# VisualightMicroDIY_02.net
KiCad netlist of a schematic drawn in EAGLE
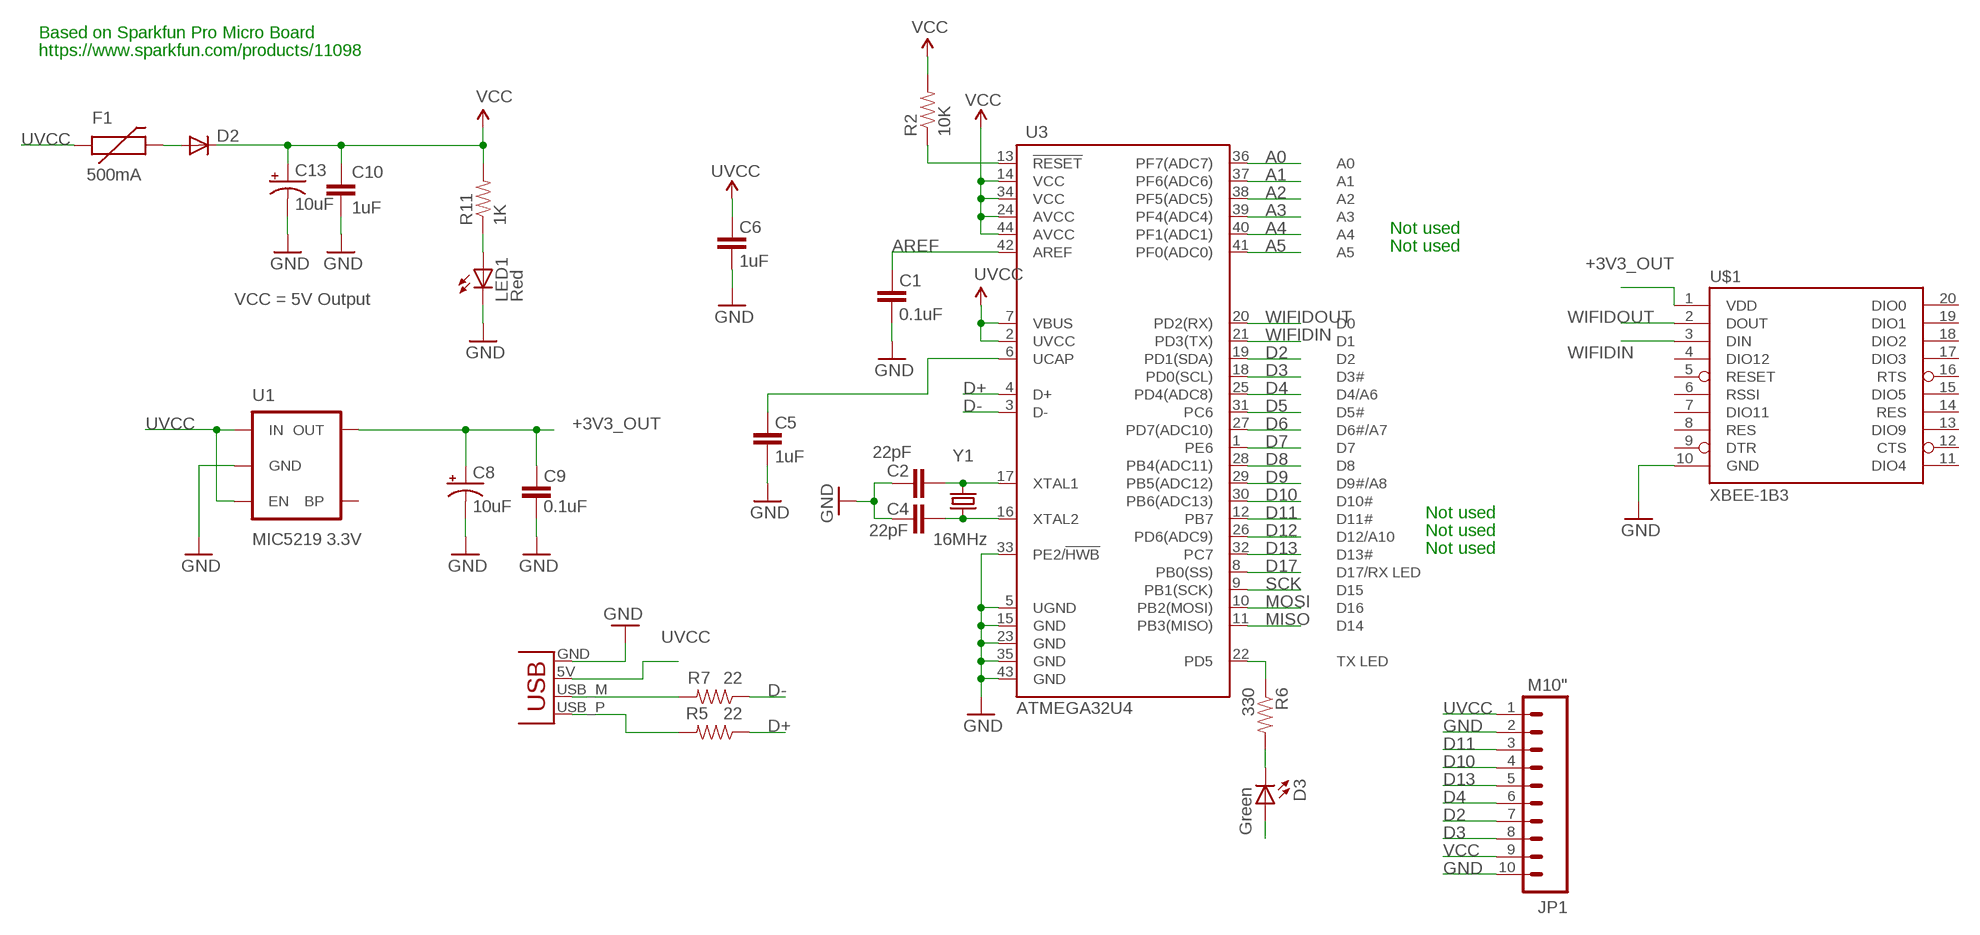
[diagram p0: schematic, sheet 1]

(export (version "E")
  (design (tool "Eeschema 10.0.6"))
  (components
    (comp (ref "C1")
      (value "0.1uF")
      (footprint "eagle-import:0402-CAP")
      (libsource (lib "eagle-import") (part "CAP0402-CAP"))
    )
    (comp (ref "C2")
      (value "22pF")
      (footprint "eagle-import:0402-CAP")
      (libsource (lib "eagle-import") (part "CAP0402-CAP"))
    )
    (comp (ref "C4")
      (value "22pF")
      (footprint "eagle-import:0402-CAP")
      (libsource (lib "eagle-import") (part "CAP0402-CAP"))
    )
    (comp (ref "C5")
      (value "1uF")
      (footprint "eagle-import:0402-CAP")
      (libsource (lib "eagle-import") (part "CAP0402-CAP"))
    )
    (comp (ref "C6")
      (value "1uF")
      (footprint "eagle-import:0402-CAP")
      (libsource (lib "eagle-import") (part "CAP0402-CAP"))
    )
    (comp (ref "C8")
      (value "10uF")
      (footprint "eagle-import:EIA3216")
      (libsource (lib "eagle-import") (part "CAP_POL1206"))
    )
    (comp (ref "C9")
      (value "0.1uF")
      (footprint "eagle-import:0402-CAP")
      (libsource (lib "eagle-import") (part "CAP0402-CAP"))
    )
    (comp (ref "C10")
      (value "1uF")
      (footprint "eagle-import:0402-CAP")
      (libsource (lib "eagle-import") (part "CAP0402-CAP"))
    )
    (comp (ref "C13")
      (value "10uF")
      (footprint "eagle-import:EIA3216")
      (libsource (lib "eagle-import") (part "CAP_POL1206"))
    )
    (comp (ref "D2")
      (value "DIODESOD")
      (footprint "eagle-import:SOD-323")
      (libsource (lib "eagle-import") (part "DIODESOD"))
    )
    (comp (ref "D3")
      (value "Green")
      (footprint "eagle-import:LED-0603")
      (libsource (lib "eagle-import") (part "LED0603"))
    )
    (comp (ref "F1")
      (value "500mA")
      (footprint "eagle-import:PTC-1206")
      (libsource (lib "eagle-import") (part "PTCSMD"))
    )
    (comp (ref "JP1")
      (value "M10\"")
      (footprint "eagle-import:1X10")
      (libsource (lib "eagle-import") (part "M10{dblquote}"))
    )
    (comp (ref "LED1")
      (value "Red")
      (footprint "eagle-import:LED-0603")
      (libsource (lib "eagle-import") (part "LED0603"))
    )
    (comp (ref "R2")
      (value "10K")
      (footprint "eagle-import:0402-RES")
      (libsource (lib "eagle-import") (part "RESISTOR0402-RES"))
    )
    (comp (ref "R5")
      (value "22")
      (footprint "eagle-import:0402-RES")
      (libsource (lib "eagle-import") (part "RESISTOR0402-RES"))
    )
    (comp (ref "R6")
      (value "330")
      (footprint "eagle-import:0402-RES")
      (libsource (lib "eagle-import") (part "RESISTOR0402-RES"))
    )
    (comp (ref "R7")
      (value "22")
      (footprint "eagle-import:0402-RES")
      (libsource (lib "eagle-import") (part "RESISTOR0402-RES"))
    )
    (comp (ref "R11")
      (value "1K")
      (footprint "eagle-import:0402-RES")
      (libsource (lib "eagle-import") (part "RESISTOR0402-RES"))
    )
    (comp (ref "U$1")
      (value "XBEE-1B3")
      (footprint "eagle-import:XBEE-SMD")
      (libsource (lib "eagle-import") (part "XBEE-1B3"))
    )
    (comp (ref "U1")
      (value "MIC5219 3.3V")
      (footprint "eagle-import:SOT23-5")
      (libsource (lib "eagle-import") (part "V_REG_MIC52193.3V"))
    )
    (comp (ref "U3")
      (value "ATMEGA32U4")
      (footprint "eagle-import:SPARKFUN-DIGITALIC_TQFP44")
      (libsource (lib "eagle-import") (part "ATMEGA32U4TQFP"))
    )
    (comp (ref "X2")
      (value "USBPCB")
      (footprint "eagle-import:USB-A-PCB")
      (libsource (lib "eagle-import") (part "USBPCB"))
    )
    (comp (ref "Y1")
      (value "16MHz")
      (footprint "eagle-import:CRYSTAL-SMD-5X3")
      (libsource (lib "eagle-import") (part "CRYSTAL5X3"))
    )
  )
  (nets
    (net (code "1") (name "/+3V3_OUT") (class "Default")
      (node (ref "C8") (pin "A") (pinfunction "+_A") (pintype "passive"))
      (node (ref "C9") (pin "2") (pinfunction "2_2") (pintype "passive"))
      (node (ref "U$1") (pin "1") (pinfunction "VDD_1") (pintype "power_in"))
      (node (ref "U1") (pin "5") (pinfunction "OUT_5") (pintype "passive"))
    )
    (net (code "2") (name "/A0") (class "Default")
      (node (ref "U3") (pin "36") (pinfunction "PF7(ADC7)_36") (pintype "bidirectional"))
    )
    (net (code "3") (name "/A1") (class "Default")
      (node (ref "U3") (pin "37") (pinfunction "PF6(ADC6)_37") (pintype "bidirectional"))
    )
    (net (code "4") (name "/A2") (class "Default")
      (node (ref "U3") (pin "38") (pinfunction "PF5(ADC5)_38") (pintype "bidirectional"))
    )
    (net (code "5") (name "/A3") (class "Default")
      (node (ref "U3") (pin "39") (pinfunction "PF4(ADC4)_39") (pintype "bidirectional"))
    )
    (net (code "6") (name "/A4") (class "Default")
      (node (ref "U3") (pin "40") (pinfunction "PF1(ADC1)_40") (pintype "bidirectional"))
    )
    (net (code "7") (name "/A5") (class "Default")
      (node (ref "U3") (pin "41") (pinfunction "PF0(ADC0)_41") (pintype "bidirectional"))
    )
    (net (code "8") (name "/AREF") (class "Default")
      (node (ref "C1") (pin "2") (pinfunction "2_2") (pintype "passive"))
      (node (ref "U3") (pin "42") (pinfunction "AREF_42") (pintype "bidirectional"))
    )
    (net (code "9") (name "/D+") (class "Default")
      (node (ref "R5") (pin "1") (pinfunction "1_1") (pintype "passive"))
      (node (ref "U3") (pin "4") (pinfunction "D+_4") (pintype "bidirectional"))
    )
    (net (code "10") (name "/D-") (class "Default")
      (node (ref "R7") (pin "1") (pinfunction "1_1") (pintype "passive"))
      (node (ref "U3") (pin "3") (pinfunction "D-_3") (pintype "bidirectional"))
    )
    (net (code "11") (name "/D2") (class "Default")
      (node (ref "JP1") (pin "7") (pinfunction "7_7") (pintype "passive"))
      (node (ref "U3") (pin "19") (pinfunction "PD1(SDA)_19") (pintype "bidirectional"))
    )
    (net (code "12") (name "/D3") (class "Default")
      (node (ref "JP1") (pin "8") (pinfunction "8_8") (pintype "passive"))
      (node (ref "U3") (pin "18") (pinfunction "PD0(SCL)_18") (pintype "bidirectional"))
    )
    (net (code "13") (name "/D4") (class "Default")
      (node (ref "JP1") (pin "6") (pinfunction "6_6") (pintype "passive"))
      (node (ref "U3") (pin "25") (pinfunction "PD4(ADC8)_25") (pintype "bidirectional"))
    )
    (net (code "14") (name "/D5") (class "Default")
      (node (ref "U3") (pin "31") (pinfunction "PC6_31") (pintype "bidirectional"))
    )
    (net (code "15") (name "/D6") (class "Default")
      (node (ref "U3") (pin "27") (pinfunction "PD7(ADC10)_27") (pintype "bidirectional"))
    )
    (net (code "16") (name "/D7") (class "Default")
      (node (ref "U3") (pin "1") (pinfunction "PE6_1") (pintype "bidirectional"))
    )
    (net (code "17") (name "/D8") (class "Default")
      (node (ref "U3") (pin "28") (pinfunction "PB4(ADC11)_28") (pintype "bidirectional"))
    )
    (net (code "18") (name "/D9") (class "Default")
      (node (ref "U3") (pin "29") (pinfunction "PB5(ADC12)_29") (pintype "bidirectional"))
    )
    (net (code "19") (name "/D10") (class "Default")
      (node (ref "JP1") (pin "4") (pinfunction "4_4") (pintype "passive"))
      (node (ref "U3") (pin "30") (pinfunction "PB6(ADC13)_30") (pintype "bidirectional"))
    )
    (net (code "20") (name "/D11") (class "Default")
      (node (ref "JP1") (pin "3") (pinfunction "3_3") (pintype "passive"))
      (node (ref "U3") (pin "12") (pinfunction "PB7_12") (pintype "bidirectional"))
    )
    (net (code "21") (name "/D12") (class "Default")
      (node (ref "U3") (pin "26") (pinfunction "PD6(ADC9)_26") (pintype "bidirectional"))
    )
    (net (code "22") (name "/D13") (class "Default")
      (node (ref "JP1") (pin "5") (pinfunction "5_5") (pintype "passive"))
      (node (ref "U3") (pin "32") (pinfunction "PC7_32") (pintype "bidirectional"))
    )
    (net (code "23") (name "/D17") (class "Default")
      (node (ref "U3") (pin "8") (pinfunction "PB0(SS)_8") (pintype "bidirectional"))
    )
    (net (code "24") (name "/MISO") (class "Default")
      (node (ref "U3") (pin "11") (pinfunction "PB3(MISO)_11") (pintype "bidirectional"))
    )
    (net (code "25") (name "/MOSI") (class "Default")
      (node (ref "U3") (pin "10") (pinfunction "PB2(MOSI)_10") (pintype "bidirectional"))
    )
    (net (code "26") (name "/SCK") (class "Default")
      (node (ref "U3") (pin "9") (pinfunction "PB1(SCK)_9") (pintype "bidirectional"))
    )
    (net (code "27") (name "/WIFIDIN") (class "Default")
      (node (ref "U$1") (pin "3") (pinfunction "DIN_3") (pintype "input"))
      (node (ref "U3") (pin "21") (pinfunction "PD3(TX)_21") (pintype "bidirectional"))
    )
    (net (code "28") (name "/WIFIDOUT") (class "Default")
      (node (ref "U$1") (pin "2") (pinfunction "DOUT_2") (pintype "output"))
      (node (ref "U3") (pin "20") (pinfunction "PD2(RX)_20") (pintype "bidirectional"))
    )
    (net (code "29") (name "GND") (class "Default")
      (node (ref "C1") (pin "1") (pinfunction "1_1") (pintype "passive"))
      (node (ref "C10") (pin "2") (pinfunction "2_2") (pintype "passive"))
      (node (ref "C13") (pin "C") (pinfunction "-_C") (pintype "passive"))
      (node (ref "C2") (pin "2") (pinfunction "2_2") (pintype "passive"))
      (node (ref "C4") (pin "2") (pinfunction "2_2") (pintype "passive"))
      (node (ref "C5") (pin "1") (pinfunction "1_1") (pintype "passive"))
      (node (ref "C6") (pin "1") (pinfunction "1_1") (pintype "passive"))
      (node (ref "C8") (pin "C") (pinfunction "-_C") (pintype "passive"))
      (node (ref "C9") (pin "1") (pinfunction "1_1") (pintype "passive"))
      (node (ref "JP1") (pin "10") (pinfunction "10_10") (pintype "passive"))
      (node (ref "JP1") (pin "2") (pinfunction "2_2") (pintype "passive"))
      (node (ref "LED1") (pin "C") (pinfunction "C_C") (pintype "passive"))
      (node (ref "U$1") (pin "10") (pinfunction "GND_10") (pintype "power_in"))
      (node (ref "U1") (pin "2") (pinfunction "GND_2") (pintype "input"))
      (node (ref "U3") (pin "15") (pinfunction "GND_15") (pintype "bidirectional"))
      (node (ref "U3") (pin "23") (pinfunction "GND_23") (pintype "bidirectional"))
      (node (ref "U3") (pin "33") (pinfunction "PE2/~{HWB}_33") (pintype "bidirectional"))
      (node (ref "U3") (pin "35") (pinfunction "GND_35") (pintype "bidirectional"))
      (node (ref "U3") (pin "43") (pinfunction "GND_43") (pintype "bidirectional"))
      (node (ref "U3") (pin "5") (pinfunction "UGND_5") (pintype "bidirectional"))
      (node (ref "X2") (pin "GND") (pinfunction "GND_GND") (pintype "bidirectional"))
    )
    (net (code "30") (name "Net-(D2-A)") (class "Default")
      (node (ref "D2") (pin "2") (pinfunction "A_2") (pintype "passive"))
      (node (ref "F1") (pin "2") (pinfunction "2_2") (pintype "bidirectional"))
    )
    (net (code "31") (name "Net-(D3-PadC)") (class "Default")
      (node (ref "D3") (pin "C") (pinfunction "C_C") (pintype "passive"))
      (node (ref "R6") (pin "2") (pinfunction "2_2") (pintype "passive"))
    )
    (net (code "32") (name "Net-(LED1-PadA)") (class "Default")
      (node (ref "LED1") (pin "A") (pinfunction "A_A") (pintype "passive"))
      (node (ref "R11") (pin "1") (pinfunction "1_1") (pintype "passive"))
    )
    (net (code "33") (name "Net-(U3-PD5)") (class "Default")
      (node (ref "R6") (pin "1") (pinfunction "1_1") (pintype "passive"))
      (node (ref "U3") (pin "22") (pinfunction "PD5_22") (pintype "bidirectional"))
    )
    (net (code "34") (name "Net-(U3-UCAP)") (class "Default")
      (node (ref "C5") (pin "2") (pinfunction "2_2") (pintype "passive"))
      (node (ref "U3") (pin "6") (pinfunction "UCAP_6") (pintype "bidirectional"))
    )
    (net (code "35") (name "Net-(U3-XTAL1)") (class "Default")
      (node (ref "C2") (pin "1") (pinfunction "1_1") (pintype "passive"))
      (node (ref "U3") (pin "17") (pinfunction "XTAL1_17") (pintype "bidirectional"))
      (node (ref "Y1") (pin "3") (pinfunction "2_3") (pintype "passive"))
    )
    (net (code "36") (name "Net-(U3-XTAL2)") (class "Default")
      (node (ref "C4") (pin "1") (pinfunction "1_1") (pintype "passive"))
      (node (ref "U3") (pin "16") (pinfunction "XTAL2_16") (pintype "bidirectional"))
      (node (ref "Y1") (pin "1") (pinfunction "1_1") (pintype "passive"))
    )
    (net (code "37") (name "Net-(U3-~{RESET})") (class "Default")
      (node (ref "R2") (pin "1") (pinfunction "1_1") (pintype "passive"))
      (node (ref "U3") (pin "13") (pinfunction "~{RESET}_13") (pintype "bidirectional"))
    )
    (net (code "38") (name "Net-(X2-D+)") (class "Default")
      (node (ref "R5") (pin "2") (pinfunction "2_2") (pintype "passive"))
      (node (ref "X2") (pin "USB_P") (pinfunction "D+_USB_P") (pintype "bidirectional"))
    )
    (net (code "39") (name "Net-(X2-D-)") (class "Default")
      (node (ref "R7") (pin "2") (pinfunction "2_2") (pintype "passive"))
      (node (ref "X2") (pin "USB_M") (pinfunction "D-_USB_M") (pintype "bidirectional"))
    )
    (net (code "40") (name "UVCC") (class "Default")
      (node (ref "C6") (pin "2") (pinfunction "2_2") (pintype "passive"))
      (node (ref "D3") (pin "A") (pinfunction "A_A") (pintype "passive"))
      (node (ref "F1") (pin "1") (pinfunction "1_1") (pintype "bidirectional"))
      (node (ref "JP1") (pin "1") (pinfunction "1_1") (pintype "passive"))
      (node (ref "U1") (pin "1") (pinfunction "IN_1") (pintype "input"))
      (node (ref "U1") (pin "3") (pinfunction "EN_3") (pintype "input"))
      (node (ref "U3") (pin "2") (pinfunction "UVCC_2") (pintype "bidirectional"))
      (node (ref "U3") (pin "7") (pinfunction "VBUS_7") (pintype "bidirectional"))
      (node (ref "X2") (pin "5V") (pinfunction "VBUS_5V") (pintype "bidirectional"))
    )
    (net (code "41") (name "VCC") (class "Default")
      (node (ref "C10") (pin "1") (pinfunction "1_1") (pintype "passive"))
      (node (ref "C13") (pin "A") (pinfunction "+_A") (pintype "passive"))
      (node (ref "D2") (pin "1") (pinfunction "C_1") (pintype "passive"))
      (node (ref "JP1") (pin "9") (pinfunction "9_9") (pintype "passive"))
      (node (ref "R11") (pin "2") (pinfunction "2_2") (pintype "passive"))
      (node (ref "R2") (pin "2") (pinfunction "2_2") (pintype "passive"))
      (node (ref "U3") (pin "14") (pinfunction "VCC_14") (pintype "bidirectional"))
      (node (ref "U3") (pin "24") (pinfunction "AVCC_24") (pintype "bidirectional"))
      (node (ref "U3") (pin "34") (pinfunction "VCC_34") (pintype "bidirectional"))
      (node (ref "U3") (pin "44") (pinfunction "AVCC_44") (pintype "bidirectional"))
    )
    (net (code "42") (name "unconnected-(U$1-CTS-Pad12)") (class "Default")
      (node (ref "U$1") (pin "12") (pinfunction "CTS_12") (pintype "output"))
    )
    (net (code "43") (name "unconnected-(U$1-DIO0-Pad20)") (class "Default")
      (node (ref "U$1") (pin "20") (pinfunction "DIO0_20") (pintype "bidirectional"))
    )
    (net (code "44") (name "unconnected-(U$1-DIO1-Pad19)") (class "Default")
      (node (ref "U$1") (pin "19") (pinfunction "DIO1_19") (pintype "bidirectional"))
    )
    (net (code "45") (name "unconnected-(U$1-DIO2-Pad18)") (class "Default")
      (node (ref "U$1") (pin "18") (pinfunction "DIO2_18") (pintype "bidirectional"))
    )
    (net (code "46") (name "unconnected-(U$1-DIO3-Pad17)") (class "Default")
      (node (ref "U$1") (pin "17") (pinfunction "DIO3_17") (pintype "bidirectional"))
    )
    (net (code "47") (name "unconnected-(U$1-DIO4-Pad11)") (class "Default")
      (node (ref "U$1") (pin "11") (pinfunction "DIO4_11") (pintype "bidirectional"))
    )
    (net (code "48") (name "unconnected-(U$1-DIO5-Pad15)") (class "Default")
      (node (ref "U$1") (pin "15") (pinfunction "DIO5_15") (pintype "bidirectional"))
    )
    (net (code "49") (name "unconnected-(U$1-DIO9-Pad13)") (class "Default")
      (node (ref "U$1") (pin "13") (pinfunction "DIO9_13") (pintype "bidirectional"))
    )
    (net (code "50") (name "unconnected-(U$1-DIO11-Pad7)") (class "Default")
      (node (ref "U$1") (pin "7") (pinfunction "DIO11_7") (pintype "bidirectional"))
    )
    (net (code "51") (name "unconnected-(U$1-DIO12-Pad4)") (class "Default")
      (node (ref "U$1") (pin "4") (pinfunction "DIO12_4") (pintype "bidirectional"))
    )
    (net (code "52") (name "unconnected-(U$1-DTR-Pad9)") (class "Default")
      (node (ref "U$1") (pin "9") (pinfunction "DTR_9") (pintype "bidirectional"))
    )
    (net (code "53") (name "unconnected-(U$1-RES-Pad8)") (class "Default")
      (node (ref "U$1") (pin "8") (pinfunction "RES_8") (pintype "bidirectional"))
    )
    (net (code "54") (name "unconnected-(U$1-RES-Pad14)") (class "Default")
      (node (ref "U$1") (pin "14") (pinfunction "RES_14") (pintype "bidirectional"))
    )
    (net (code "55") (name "unconnected-(U$1-RESET-Pad5)") (class "Default")
      (node (ref "U$1") (pin "5") (pinfunction "RESET_5") (pintype "input"))
    )
    (net (code "56") (name "unconnected-(U$1-RSSI-Pad6)") (class "Default")
      (node (ref "U$1") (pin "6") (pinfunction "RSSI_6") (pintype "bidirectional"))
    )
    (net (code "57") (name "unconnected-(U$1-RTS-Pad16)") (class "Default")
      (node (ref "U$1") (pin "16") (pinfunction "RTS_16") (pintype "input"))
    )
    (net (code "58") (name "unconnected-(U1-BP-Pad4)") (class "Default")
      (node (ref "U1") (pin "4") (pinfunction "BP_4") (pintype "input"))
    )
  )
)
